# 1_-_Power.net
KiCad netlist of a schematic drawn in Altium Designer
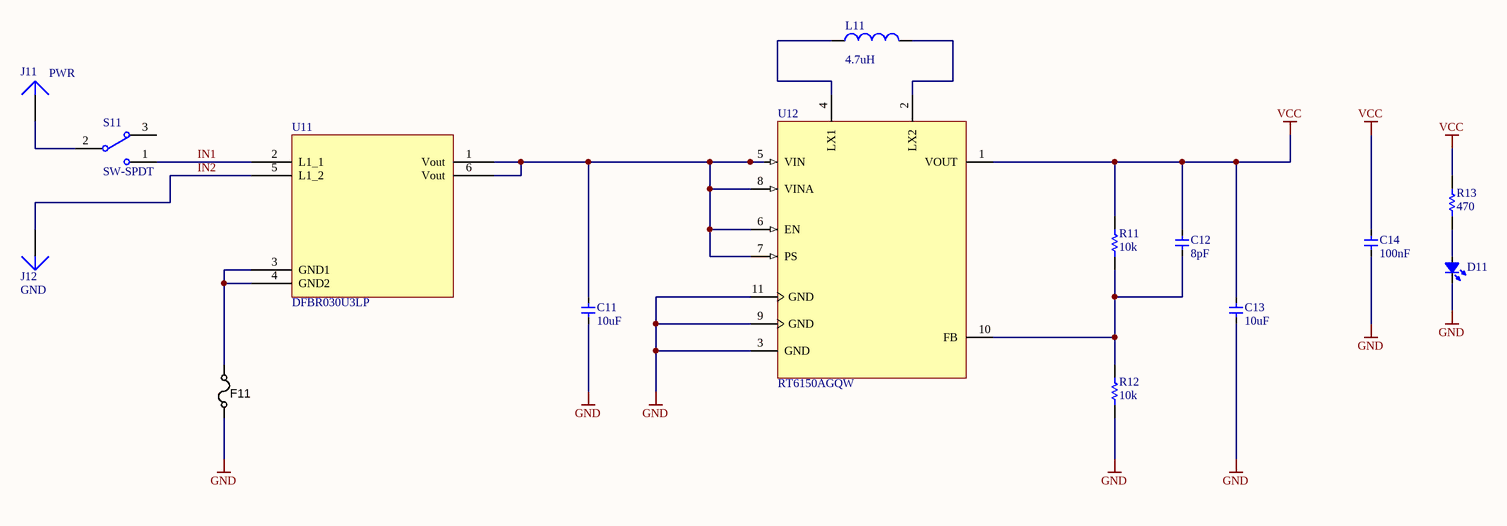
[diagram p0: 1 - Power.SchDoc]

(export (version "E")
  (design (tool "Eeschema 10.0.6"))
  (components
    (comp (ref "C11")
      (value "10uF")
      (footprint "CAPC2012X135N")
      (description "Capacitor")
      (fields (field (name "Comment") "Cap_0603"))
      (libsource (lib "SCH_Passive") (part "Cap_0603"))
    )
    (comp (ref "C12")
      (value "8pF")
      (footprint "PCB_PassiveCap:CAP_0603")
      (description "Capacitor")
      (fields (field (name "Comment") "Cap_0603"))
      (libsource (lib "SCH_Passive") (part "Cap_0603"))
    )
    (comp (ref "C13")
      (value "10uF")
      (footprint "CAPC2012X135N")
      (description "Capacitor")
      (fields (field (name "Comment") "Cap_0603"))
      (libsource (lib "SCH_Passive") (part "Cap_0603"))
    )
    (comp (ref "C14")
      (value "100nF")
      (footprint "PCB_PassiveCap:CAP_0603")
      (description "Capacitor")
      (fields (field (name "Comment") "Cap_0603"))
      (libsource (lib "SCH_Passive") (part "Cap_0603"))
    )
    (comp (ref "D11")
      (value "LED_0603")
      (footprint "PCB_ActiveLED:LED_0603_RED")
      (description "LED")
      (libsource (lib "SCH_Active") (part "LED_0603"))
    )
    (comp (ref "F11")
      (value "Slow-blow")
      (footprint "RESC3216X70N")
      (description "Fuse 750mA 6VDC 1206 SMD")
      (libsource (lib "PBL - Fuses and Protection") (part "FUSE_160mA_1206"))
    )
    (comp (ref "J11")
      (value "PWR")
      (footprint "PIN1")
      (description "Plug")
      (fields (field (name "PUBLISHER") "Altium Limited"))
      (libsource (lib "Miscellaneous Connectors") (part "Plug"))
    )
    (comp (ref "J12")
      (value "GND")
      (footprint "PIN1")
      (description "Plug")
      (fields (field (name "PUBLISHER") "Altium Limited"))
      (libsource (lib "Miscellaneous Connectors") (part "Plug"))
    )
    (comp (ref "L11")
      (value "4.7uH")
      (footprint "RES_0805")
      (description "Inductor")
      (fields (field (name "PUBLISHER") "Altium Limited"))
      (libsource (lib "Miscellaneous Devices") (part "Inductor"))
    )
    (comp (ref "R11")
      (value "10k")
      (footprint "RES_0603")
      (description "Resistor")
      (fields (field (name "Comment") "Res1") (field (name "PUBLISHER") "Altium Limited"))
      (libsource (lib "Miscellaneous Devices") (part "Res1"))
    )
    (comp (ref "R12")
      (value "10k")
      (footprint "RES_0603")
      (description "Resistor")
      (fields (field (name "Comment") "Res1") (field (name "PUBLISHER") "Altium Limited"))
      (libsource (lib "Miscellaneous Devices") (part "Res1"))
    )
    (comp (ref "R13")
      (value "470")
      (footprint "RES_0603")
      (description "Resistor")
      (fields (field (name "Comment") "Res1") (field (name "PUBLISHER") "Altium Limited"))
      (libsource (lib "Miscellaneous Devices") (part "Res1"))
    )
    (comp (ref "S11")
      (value "SW-SPDT")
      (footprint "MSK-12C02")
      (description "SPDT Subminiature Toggle Switch, Right Angle Mounting, Vertical Actuation")
      (fields (field (name "PUBLISHER") "Altium Limited"))
      (libsource (lib "Jarrett") (part "SW-SPDT"))
    )
    (comp (ref "U11")
      (value "DFBR030U3LP")
      (footprint "Jarrett:U-DFN4040-8")
      (description "3A Full Bridge Rectifier")
      (libsource (lib "Jarrett") (part "DFBR030U3LP"))
    )
    (comp (ref "U12")
      (value "RT6150AGQW")
      (footprint "DFN-MF10")
      (description "Buck-Boost Switching Regulator IC Positive Adjustable 1.8V 1 Output 800mA 10-WFDFN Exposed Pad")
      (libsource (lib "Jarrett") (part "RT6150AGQW"))
    )
  )
  (nets
    (net (code "1") (name "/IN1") (class "Default")
      (node (ref "S11") (pin "1") (pinfunction "1_1") (pintype "passive"))
      (node (ref "U11") (pin "2") (pinfunction "L1_1_2") (pintype "passive"))
    )
    (net (code "2") (name "/IN2") (class "Default")
      (node (ref "J12") (pin "1") (pinfunction "1_1") (pintype "passive"))
      (node (ref "U11") (pin "5") (pinfunction "L1_2_5") (pintype "passive"))
    )
    (net (code "3") (name "GND") (class "Default")
      (node (ref "C11") (pin "1") (pinfunction "1_1") (pintype "passive"))
      (node (ref "C13") (pin "1") (pinfunction "1_1") (pintype "passive"))
      (node (ref "C14") (pin "1") (pinfunction "1_1") (pintype "passive"))
      (node (ref "D11") (pin "2") (pinfunction "K_2") (pintype "passive"))
      (node (ref "F11") (pin "1") (pinfunction "1_1") (pintype "passive"))
      (node (ref "R12") (pin "1") (pinfunction "1_1") (pintype "passive"))
      (node (ref "U12") (pin "11") (pinfunction "GND_11") (pintype "power_in"))
      (node (ref "U12") (pin "3") (pinfunction "GND_3") (pintype "power_in"))
      (node (ref "U12") (pin "9") (pinfunction "GND_9") (pintype "power_in"))
    )
    (net (code "4") (name "Net-(D11-A)") (class "Default")
      (node (ref "D11") (pin "1") (pinfunction "A_1") (pintype "passive"))
      (node (ref "R13") (pin "1") (pinfunction "1_1") (pintype "passive"))
    )
    (net (code "5") (name "Net-(J11-Pad1)") (class "Default")
      (node (ref "J11") (pin "1") (pinfunction "1_1") (pintype "passive"))
      (node (ref "S11") (pin "2") (pinfunction "2_2") (pintype "passive"))
    )
    (net (code "6") (name "Net-(U11-GND1)") (class "Default")
      (node (ref "F11") (pin "2") (pinfunction "2_2") (pintype "passive"))
      (node (ref "U11") (pin "3") (pinfunction "GND1_3") (pintype "passive"))
      (node (ref "U11") (pin "4") (pinfunction "GND2_4") (pintype "passive"))
    )
    (net (code "7") (name "Net-(U12-EN)") (class "Default")
      (node (ref "C11") (pin "2") (pinfunction "2_2") (pintype "passive"))
      (node (ref "U11") (pin "1") (pinfunction "Vout_1") (pintype "passive"))
      (node (ref "U11") (pin "6") (pinfunction "Vout_6") (pintype "passive"))
      (node (ref "U12") (pin "5") (pinfunction "VIN_5") (pintype "input"))
      (node (ref "U12") (pin "6") (pinfunction "EN_6") (pintype "input"))
      (node (ref "U12") (pin "7") (pinfunction "PS_7") (pintype "input"))
      (node (ref "U12") (pin "8") (pinfunction "VINA_8") (pintype "input"))
    )
    (net (code "8") (name "Net-(U12-FB)") (class "Default")
      (node (ref "C12") (pin "1") (pinfunction "1_1") (pintype "passive"))
      (node (ref "R11") (pin "1") (pinfunction "1_1") (pintype "passive"))
      (node (ref "R12") (pin "2") (pinfunction "2_2") (pintype "passive"))
      (node (ref "U12") (pin "10") (pinfunction "FB_10") (pintype "passive"))
    )
    (net (code "9") (name "Net-(U12-LX1)") (class "Default")
      (node (ref "L11") (pin "1") (pinfunction "1_1") (pintype "passive"))
      (node (ref "U12") (pin "4") (pinfunction "LX1_4") (pintype "passive"))
    )
    (net (code "10") (name "Net-(U12-LX2)") (class "Default")
      (node (ref "L11") (pin "2") (pinfunction "2_2") (pintype "passive"))
      (node (ref "U12") (pin "2") (pinfunction "LX2_2") (pintype "power_in"))
    )
    (net (code "11") (name "VCC") (class "Default")
      (node (ref "C12") (pin "2") (pinfunction "2_2") (pintype "passive"))
      (node (ref "C13") (pin "2") (pinfunction "2_2") (pintype "passive"))
      (node (ref "C14") (pin "2") (pinfunction "2_2") (pintype "passive"))
      (node (ref "R11") (pin "2") (pinfunction "2_2") (pintype "passive"))
      (node (ref "R13") (pin "2") (pinfunction "2_2") (pintype "passive"))
      (node (ref "U12") (pin "1") (pinfunction "VOUT_1") (pintype "power_in"))
    )
    (net (code "12") (name "unconnected-(S11-Pad3)") (class "Default")
      (node (ref "S11") (pin "3") (pinfunction "3_3") (pintype "passive"))
    )
  )
)
